# d-phy_block.net
KiCad netlist of a schematic drawn in Altium Designer
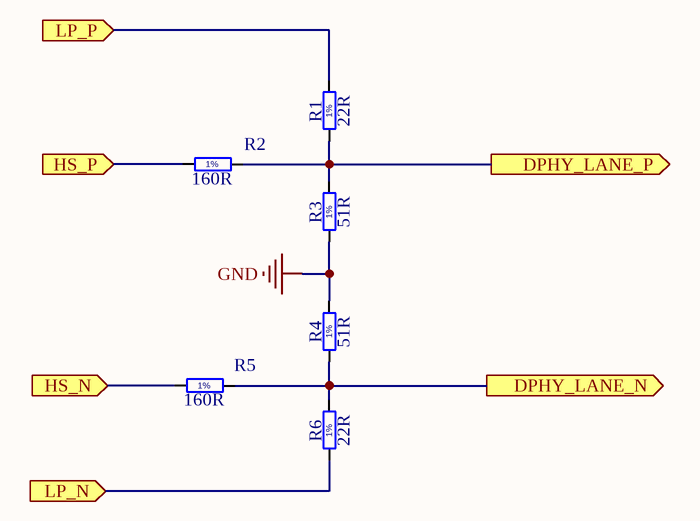
[diagram p0: d-phy_block.SchDoc]

(export (version "E")
  (design (tool "Eeschema 10.0.6"))
  (components
    (comp (ref "R1")
      (value "22R")
      (footprint "RESC1608X55N")
      (description "Resistor - 1%")
      (fields
        (field (name "PART NUMBER") "R0603_100K_1%_0.1W_100PPM")
        (field (name "POWER") "0.1W")
        (field (name "AUTHOR") "CERN DEM JLC")
      )
      (libsource (lib "Resistors") (part "Resistor - 1%"))
    )
    (comp (ref "R2")
      (value "160R")
      (footprint "RESC1608X55N")
      (description "Resistor - 1%")
      (fields
        (field (name "PART NUMBER") "R0603_100K_1%_0.1W_100PPM")
        (field (name "POWER") "0.1W")
        (field (name "AUTHOR") "CERN DEM JLC")
      )
      (libsource (lib "Resistors") (part "Resistor - 1%"))
    )
    (comp (ref "R3")
      (value "51R")
      (footprint "RESC1608X55N")
      (description "Resistor - 1%")
      (fields
        (field (name "PART NUMBER") "R0603_100K_1%_0.1W_100PPM")
        (field (name "POWER") "0.1W")
        (field (name "AUTHOR") "CERN DEM JLC")
      )
      (libsource (lib "Resistors") (part "Resistor - 1%"))
    )
    (comp (ref "R4")
      (value "51R")
      (footprint "RESC1608X55N")
      (description "Resistor - 1%")
      (fields
        (field (name "PART NUMBER") "R0603_100K_1%_0.1W_100PPM")
        (field (name "POWER") "0.1W")
        (field (name "AUTHOR") "CERN DEM JLC")
      )
      (libsource (lib "Resistors") (part "Resistor - 1%"))
    )
    (comp (ref "R5")
      (value "160R")
      (footprint "RESC1608X55N")
      (description "Resistor - 1%")
      (fields
        (field (name "PART NUMBER") "R0603_100K_1%_0.1W_100PPM")
        (field (name "POWER") "0.1W")
        (field (name "AUTHOR") "CERN DEM JLC")
      )
      (libsource (lib "Resistors") (part "Resistor - 1%"))
    )
    (comp (ref "R6")
      (value "22R")
      (footprint "RESC1608X55N")
      (description "Resistor - 1%")
      (fields
        (field (name "PART NUMBER") "R0603_100K_1%_0.1W_100PPM")
        (field (name "POWER") "0.1W")
        (field (name "AUTHOR") "CERN DEM JLC")
      )
      (libsource (lib "Resistors") (part "Resistor - 1%"))
    )
  )
  (nets
    (net (code "1") (name "/DPHY_LANE_N") (class "Default")
      (node (ref "R4") (pin "1") (pinfunction "1_1") (pintype "passive"))
      (node (ref "R5") (pin "2") (pinfunction "2_2") (pintype "passive"))
      (node (ref "R6") (pin "2") (pinfunction "2_2") (pintype "passive"))
    )
    (net (code "2") (name "/DPHY_LANE_P") (class "Default")
      (node (ref "R1") (pin "1") (pinfunction "1_1") (pintype "passive"))
      (node (ref "R2") (pin "2") (pinfunction "2_2") (pintype "passive"))
      (node (ref "R3") (pin "2") (pinfunction "2_2") (pintype "passive"))
    )
    (net (code "3") (name "/HS_N") (class "Default")
      (node (ref "R5") (pin "1") (pinfunction "1_1") (pintype "passive"))
    )
    (net (code "4") (name "/HS_P") (class "Default")
      (node (ref "R2") (pin "1") (pinfunction "1_1") (pintype "passive"))
    )
    (net (code "5") (name "/LP_N") (class "Default")
      (node (ref "R6") (pin "1") (pinfunction "1_1") (pintype "passive"))
    )
    (net (code "6") (name "/LP_P") (class "Default")
      (node (ref "R1") (pin "2") (pinfunction "2_2") (pintype "passive"))
    )
    (net (code "7") (name "GND") (class "Default")
      (node (ref "R3") (pin "1") (pinfunction "1_1") (pintype "passive"))
      (node (ref "R4") (pin "2") (pinfunction "2_2") (pintype "passive"))
    )
  )
)
